# SensorDHT22.net
KiCad netlist of a schematic drawn in EAGLE
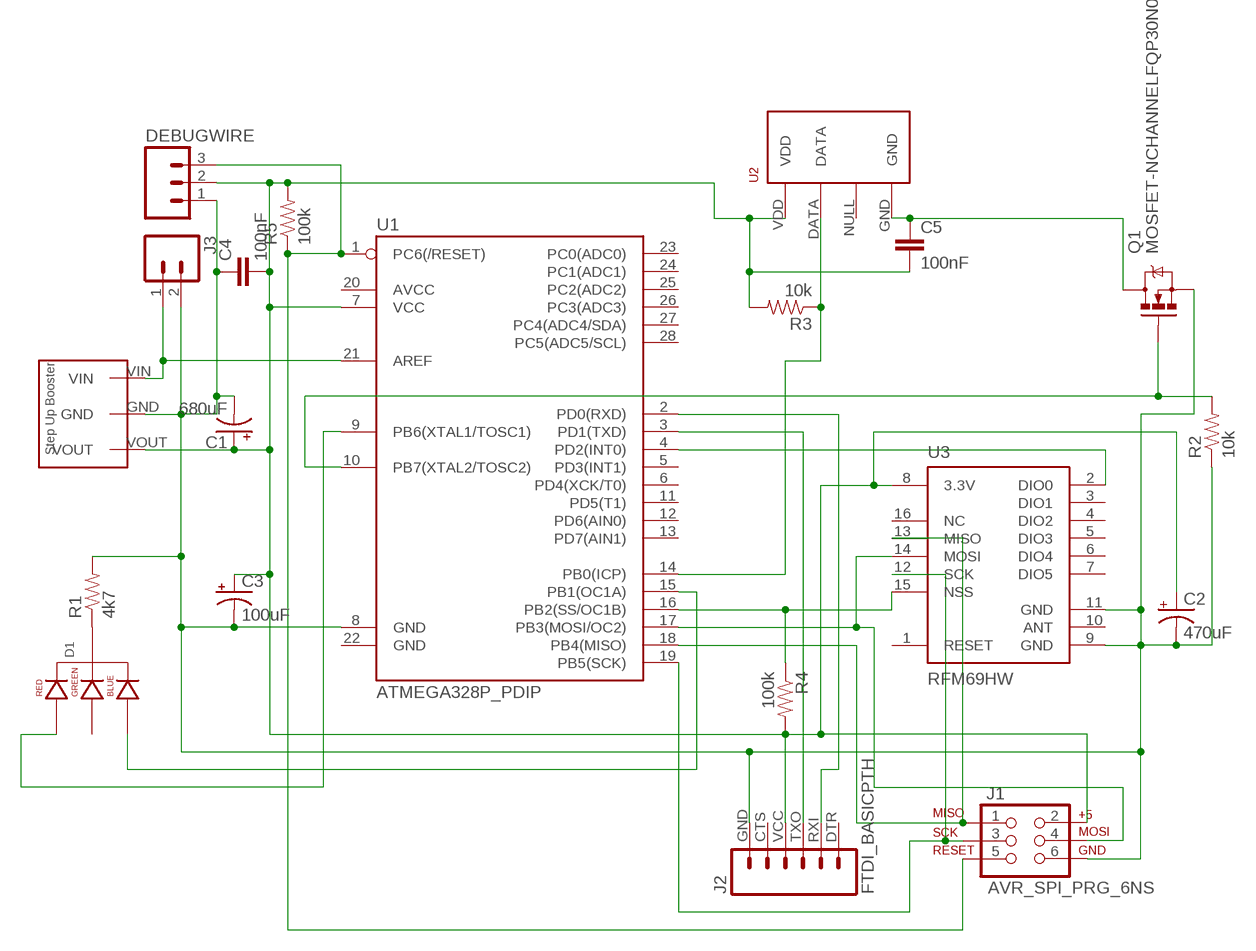
[diagram p0: schematic, sheet 1]

(export (version "E")
  (design (tool "Eeschema 10.0.6"))
  (components
    (comp (ref "C1")
      (value "680uF")
      (footprint "eagle-import:CPOL-RADIAL-100UF-25V")
      (libsource (lib "eagle-import") (part "CAP_POLPTH1"))
    )
    (comp (ref "C2")
      (value "470uF")
      (footprint "eagle-import:CPOL-RADIAL-100UF-25V")
      (libsource (lib "eagle-import") (part "CAP_POLPTH1"))
    )
    (comp (ref "C3")
      (value "100uF")
      (footprint "eagle-import:CPOL-RADIAL-10UF-25V")
      (libsource (lib "eagle-import") (part "CAP_POLPTH2"))
    )
    (comp (ref "C4")
      (value "100nF")
      (footprint "eagle-import:CAP-PTH-SMALL")
      (libsource (lib "eagle-import") (part "CAPPTH"))
    )
    (comp (ref "C5")
      (value "100nF")
      (footprint "eagle-import:CAP-PTH-SMALL")
      (libsource (lib "eagle-import") (part "CAPPTH"))
    )
    (comp (ref "D1")
      (value "LED-RGB-CC-THRUCLEAR")
      (footprint "eagle-import:LED-RGB-THRU")
      (libsource (lib "eagle-import") (part "LED-RGB-CC-THRUCLEAR"))
    )
    (comp (ref "DEBUGWIRE")
      (value "M03PTH")
      (footprint "eagle-import:1X03")
      (libsource (lib "eagle-import") (part "M03PTH"))
    )
    (comp (ref "J1")
      (value "AVR_SPI_PRG_6NS")
      (footprint "eagle-import:2X3-NS")
      (libsource (lib "eagle-import") (part "AVR_SPI_PRG_6NS"))
    )
    (comp (ref "J2")
      (value "FTDI_BASICPTH")
      (footprint "eagle-import:FTDI_BASIC")
      (libsource (lib "eagle-import") (part "FTDI_BASICPTH"))
    )
    (comp (ref "J3")
      (value "M02POLAR")
      (footprint "eagle-import:MOLEX-1X2")
      (libsource (lib "eagle-import") (part "M02POLAR"))
    )
    (comp (ref "Q1")
      (value "MOSFET-NCHANNELFQP30N06L")
      (footprint "eagle-import:TO220V")
      (libsource (lib "eagle-import") (part "MOSFET-NCHANNELFQP30N06L"))
    )
    (comp (ref "R1")
      (value "4k7")
      (footprint "eagle-import:AXIAL-0.4")
      (libsource (lib "eagle-import") (part "RESISTORPTH-1/4W"))
    )
    (comp (ref "R2")
      (value "10k")
      (footprint "eagle-import:AXIAL-0.3")
      (libsource (lib "eagle-import") (part "10KOHM-1/4W-1%(PTH)HORIZ"))
    )
    (comp (ref "R3")
      (value "10k")
      (footprint "eagle-import:AXIAL-0.3")
      (libsource (lib "eagle-import") (part "10KOHM-1/4W-1%(PTH)HORIZ"))
    )
    (comp (ref "R4")
      (value "100k")
      (footprint "eagle-import:AXIAL-0.4")
      (libsource (lib "eagle-import") (part "RESISTORPTH-1/4W"))
    )
    (comp (ref "R5")
      (value "100k")
      (footprint "eagle-import:AXIAL-0.3")
      (libsource (lib "eagle-import") (part "100KOHM-1/4W-5%(PTH)"))
    )
    (comp (ref "STEPUP")
      (value "POLOLU-2563")
      (footprint "eagle-import:POLOLU-2563")
      (libsource (lib "eagle-import") (part "POLOLU-2563"))
    )
    (comp (ref "U1")
      (value "ATMEGA328P_PDIP")
      (footprint "eagle-import:DIL28-3")
      (libsource (lib "eagle-import") (part "ATMEGA328P_PDIP"))
    )
    (comp (ref "U2")
      (value "RHT03_DHT-22_AM2302")
      (footprint "eagle-import:RHT03_DHT-22")
      (libsource (lib "eagle-import") (part "RHT03_DHT-22_AM2302"))
    )
    (comp (ref "U3")
      (value "RFM69HW")
      (footprint "eagle-import:RFM69W-XXXS2")
      (libsource (lib "eagle-import") (part "RFM69HW"))
    )
  )
  (nets
    (net (code "1") (name "Net-(C1-+)") (class "Default")
      (node (ref "C1") (pin "1") (pinfunction "+_1") (pintype "passive"))
      (node (ref "C2") (pin "1") (pinfunction "+_1") (pintype "passive"))
      (node (ref "C3") (pin "1") (pinfunction "+_1") (pintype "passive"))
      (node (ref "C4") (pin "2") (pinfunction "2_2") (pintype "passive"))
      (node (ref "C5") (pin "2") (pinfunction "2_2") (pintype "passive"))
      (node (ref "DEBUGWIRE") (pin "2") (pinfunction "2_2") (pintype "passive"))
      (node (ref "J1") (pin "2") (pinfunction "2_2") (pintype "passive"))
      (node (ref "J2") (pin "VCC") (pinfunction "4_VCC") (pintype "passive"))
      (node (ref "R3") (pin "P$2") (pinfunction "2_P$2") (pintype "passive"))
      (node (ref "R4") (pin "P$2") (pinfunction "2_P$2") (pintype "passive"))
      (node (ref "R5") (pin "P$2") (pinfunction "2_P$2") (pintype "passive"))
      (node (ref "STEPUP") (pin "VOUT") (pinfunction "VOUT_VOUT") (pintype "output"))
      (node (ref "U1") (pin "7") (pinfunction "VCC_7") (pintype "bidirectional"))
      (node (ref "U2") (pin "VDD") (pinfunction "VDD_VDD") (pintype "power_in"))
      (node (ref "U3") (pin "8") (pinfunction "3.3V_8") (pintype "power_in"))
    )
    (net (code "2") (name "Net-(C1--)") (class "Default")
      (node (ref "C1") (pin "2") (pinfunction "-_2") (pintype "passive"))
      (node (ref "C2") (pin "2") (pinfunction "-_2") (pintype "passive"))
      (node (ref "C3") (pin "2") (pinfunction "-_2") (pintype "passive"))
      (node (ref "C4") (pin "1") (pinfunction "1_1") (pintype "passive"))
      (node (ref "DEBUGWIRE") (pin "1") (pinfunction "1_1") (pintype "passive"))
      (node (ref "J1") (pin "6") (pinfunction "6_6") (pintype "passive"))
      (node (ref "J2") (pin "GND") (pinfunction "6_GND") (pintype "passive"))
      (node (ref "J3") (pin "2") (pinfunction "2_2") (pintype "passive"))
      (node (ref "Q1") (pin "3") (pinfunction "S_3") (pintype "passive"))
      (node (ref "R1") (pin "P$2") (pinfunction "2_P$2") (pintype "passive"))
      (node (ref "R2") (pin "P$1") (pinfunction "1_P$1") (pintype "passive"))
      (node (ref "STEPUP") (pin "GND") (pinfunction "GND_GND") (pintype "power_in"))
      (node (ref "U1") (pin "8") (pinfunction "GND_8") (pintype "bidirectional"))
      (node (ref "U3") (pin "11") (pinfunction "GND_11") (pintype "power_in"))
      (node (ref "U3") (pin "9") (pinfunction "GND_9") (pintype "power_in"))
    )
    (net (code "3") (name "Net-(D1-BLUE_CATHODE)") (class "Default")
      (node (ref "D1") (pin "4") (pinfunction "BLUE_CATHODE_4") (pintype "bidirectional"))
      (node (ref "U1") (pin "15") (pinfunction "PB1(OC1A)_15") (pintype "bidirectional"))
    )
    (net (code "4") (name "Net-(D1-CATHODE)") (class "Default")
      (node (ref "D1") (pin "2") (pinfunction "CATHODE_2") (pintype "bidirectional"))
      (node (ref "R1") (pin "P$1") (pinfunction "1_P$1") (pintype "passive"))
    )
    (net (code "5") (name "Net-(D1-RED_CATHODE)") (class "Default")
      (node (ref "D1") (pin "1") (pinfunction "RED_CATHODE_1") (pintype "bidirectional"))
      (node (ref "U1") (pin "9") (pinfunction "PB6(XTAL1/TOSC1)_9") (pintype "bidirectional"))
    )
    (net (code "6") (name "Net-(J2-2)") (class "Default")
      (node (ref "J2") (pin "RXI") (pinfunction "2_RXI") (pintype "passive"))
      (node (ref "U1") (pin "2") (pinfunction "PD0(RXD)_2") (pintype "bidirectional"))
    )
    (net (code "7") (name "Net-(J2-3)") (class "Default")
      (node (ref "J2") (pin "TXO") (pinfunction "3_TXO") (pintype "passive"))
      (node (ref "U1") (pin "3") (pinfunction "PD1(TXD)_3") (pintype "bidirectional"))
    )
    (net (code "8") (name "Net-(Q1-D)") (class "Default")
      (node (ref "C5") (pin "1") (pinfunction "1_1") (pintype "passive"))
      (node (ref "Q1") (pin "2") (pinfunction "D_2") (pintype "passive"))
      (node (ref "U2") (pin "GND") (pinfunction "GND_GND") (pintype "power_in"))
    )
    (net (code "9") (name "Net-(Q1-G)") (class "Default")
      (node (ref "Q1") (pin "1") (pinfunction "G_1") (pintype "passive"))
      (node (ref "R2") (pin "P$2") (pinfunction "2_P$2") (pintype "passive"))
      (node (ref "U1") (pin "10") (pinfunction "PB7(XTAL2/TOSC2)_10") (pintype "bidirectional"))
    )
    (net (code "10") (name "Net-(R3-1)") (class "Default")
      (node (ref "R3") (pin "P$1") (pinfunction "1_P$1") (pintype "passive"))
      (node (ref "U1") (pin "14") (pinfunction "PB0(ICP)_14") (pintype "bidirectional"))
      (node (ref "U2") (pin "DATA") (pinfunction "DATA_DATA") (pintype "bidirectional"))
    )
    (net (code "11") (name "Net-(R4-1)") (class "Default")
      (node (ref "R4") (pin "P$1") (pinfunction "1_P$1") (pintype "passive"))
      (node (ref "U1") (pin "16") (pinfunction "PB2(SS/OC1B)_16") (pintype "bidirectional"))
      (node (ref "U3") (pin "15") (pinfunction "NSS_15") (pintype "input"))
    )
    (net (code "12") (name "Net-(R5-1)") (class "Default")
      (node (ref "DEBUGWIRE") (pin "3") (pinfunction "3_3") (pintype "passive"))
      (node (ref "J1") (pin "5") (pinfunction "5_5") (pintype "passive"))
      (node (ref "R5") (pin "P$1") (pinfunction "1_P$1") (pintype "passive"))
      (node (ref "U1") (pin "1") (pinfunction "PC6(/RESET)_1") (pintype "bidirectional"))
    )
    (net (code "13") (name "Net-(U1-AREF)") (class "Default")
      (node (ref "J3") (pin "1") (pinfunction "1_1") (pintype "passive"))
      (node (ref "STEPUP") (pin "VIN") (pinfunction "VIN_VIN") (pintype "input"))
      (node (ref "U1") (pin "21") (pinfunction "AREF_21") (pintype "bidirectional"))
    )
    (net (code "14") (name "Net-(U1-PB3(MOSI{slash}OC2))") (class "Default")
      (node (ref "J1") (pin "4") (pinfunction "4_4") (pintype "passive"))
      (node (ref "U1") (pin "17") (pinfunction "PB3(MOSI/OC2)_17") (pintype "bidirectional"))
      (node (ref "U3") (pin "14") (pinfunction "MOSI_14") (pintype "input"))
    )
    (net (code "15") (name "Net-(U1-PB4(MISO))") (class "Default")
      (node (ref "J1") (pin "1") (pinfunction "1_1") (pintype "passive"))
      (node (ref "U1") (pin "18") (pinfunction "PB4(MISO)_18") (pintype "bidirectional"))
      (node (ref "U3") (pin "13") (pinfunction "MISO_13") (pintype "bidirectional"))
    )
    (net (code "16") (name "Net-(U1-PB5(SCK))") (class "Default")
      (node (ref "J1") (pin "3") (pinfunction "3_3") (pintype "passive"))
      (node (ref "U1") (pin "19") (pinfunction "PB5(SCK)_19") (pintype "bidirectional"))
      (node (ref "U3") (pin "12") (pinfunction "SCK_12") (pintype "input"))
    )
    (net (code "17") (name "Net-(U1-PD2(INT0))") (class "Default")
      (node (ref "U1") (pin "4") (pinfunction "PD2(INT0)_4") (pintype "bidirectional"))
      (node (ref "U3") (pin "2") (pinfunction "DIO0_2") (pintype "bidirectional"))
    )
    (net (code "18") (name "unconnected-(D1-GREEN_CATHODE-Pad3)") (class "Default")
      (node (ref "D1") (pin "3") (pinfunction "GREEN_CATHODE_3") (pintype "bidirectional"))
    )
    (net (code "19") (name "unconnected-(J2-1-PadDTR)") (class "Default")
      (node (ref "J2") (pin "DTR") (pinfunction "1_DTR") (pintype "passive"))
    )
    (net (code "20") (name "unconnected-(J2-5-PadCTS)") (class "Default")
      (node (ref "J2") (pin "CTS") (pinfunction "5_CTS") (pintype "passive"))
    )
    (net (code "21") (name "unconnected-(U1-AVCC-Pad20)") (class "Default")
      (node (ref "U1") (pin "20") (pinfunction "AVCC_20") (pintype "bidirectional"))
    )
    (net (code "22") (name "unconnected-(U1-GND-Pad22)") (class "Default")
      (node (ref "U1") (pin "22") (pinfunction "GND_22") (pintype "bidirectional"))
    )
    (net (code "23") (name "unconnected-(U1-PC0(ADC0)-Pad23)") (class "Default")
      (node (ref "U1") (pin "23") (pinfunction "PC0(ADC0)_23") (pintype "bidirectional"))
    )
    (net (code "24") (name "unconnected-(U1-PC1(ADC1)-Pad24)") (class "Default")
      (node (ref "U1") (pin "24") (pinfunction "PC1(ADC1)_24") (pintype "bidirectional"))
    )
    (net (code "25") (name "unconnected-(U1-PC2(ADC2)-Pad25)") (class "Default")
      (node (ref "U1") (pin "25") (pinfunction "PC2(ADC2)_25") (pintype "bidirectional"))
    )
    (net (code "26") (name "unconnected-(U1-PC3(ADC3)-Pad26)") (class "Default")
      (node (ref "U1") (pin "26") (pinfunction "PC3(ADC3)_26") (pintype "bidirectional"))
    )
    (net (code "27") (name "unconnected-(U1-PC4(ADC4{slash}SDA)-Pad27)") (class "Default")
      (node (ref "U1") (pin "27") (pinfunction "PC4(ADC4/SDA)_27") (pintype "bidirectional"))
    )
    (net (code "28") (name "unconnected-(U1-PC5(ADC5{slash}SCL)-Pad28)") (class "Default")
      (node (ref "U1") (pin "28") (pinfunction "PC5(ADC5/SCL)_28") (pintype "bidirectional"))
    )
    (net (code "29") (name "unconnected-(U1-PD3(INT1)-Pad5)") (class "Default")
      (node (ref "U1") (pin "5") (pinfunction "PD3(INT1)_5") (pintype "bidirectional"))
    )
    (net (code "30") (name "unconnected-(U1-PD4(XCK{slash}T0)-Pad6)") (class "Default")
      (node (ref "U1") (pin "6") (pinfunction "PD4(XCK/T0)_6") (pintype "bidirectional"))
    )
    (net (code "31") (name "unconnected-(U1-PD5(T1)-Pad11)") (class "Default")
      (node (ref "U1") (pin "11") (pinfunction "PD5(T1)_11") (pintype "bidirectional"))
    )
    (net (code "32") (name "unconnected-(U1-PD6(AIN0)-Pad12)") (class "Default")
      (node (ref "U1") (pin "12") (pinfunction "PD6(AIN0)_12") (pintype "bidirectional"))
    )
    (net (code "33") (name "unconnected-(U1-PD7(AIN1)-Pad13)") (class "Default")
      (node (ref "U1") (pin "13") (pinfunction "PD7(AIN1)_13") (pintype "bidirectional"))
    )
    (net (code "34") (name "unconnected-(U2-PadNULL)") (class "Default")
      (node (ref "U2") (pin "NULL") (pinfunction "NULL_NULL") (pintype "no_connect"))
    )
    (net (code "35") (name "unconnected-(U3-ANT-Pad10)") (class "Default")
      (node (ref "U3") (pin "10") (pinfunction "ANT_10") (pintype "passive"))
    )
    (net (code "36") (name "unconnected-(U3-DIO1-Pad3)") (class "Default")
      (node (ref "U3") (pin "3") (pinfunction "DIO1_3") (pintype "bidirectional"))
    )
    (net (code "37") (name "unconnected-(U3-DIO2-Pad4)") (class "Default")
      (node (ref "U3") (pin "4") (pinfunction "DIO2_4") (pintype "bidirectional"))
    )
    (net (code "38") (name "unconnected-(U3-DIO3-Pad5)") (class "Default")
      (node (ref "U3") (pin "5") (pinfunction "DIO3_5") (pintype "bidirectional"))
    )
    (net (code "39") (name "unconnected-(U3-DIO4-Pad6)") (class "Default")
      (node (ref "U3") (pin "6") (pinfunction "DIO4_6") (pintype "bidirectional"))
    )
    (net (code "40") (name "unconnected-(U3-DIO5-Pad7)") (class "Default")
      (node (ref "U3") (pin "7") (pinfunction "DIO5_7") (pintype "bidirectional"))
    )
    (net (code "41") (name "unconnected-(U3-NC-Pad16)") (class "Default")
      (node (ref "U3") (pin "16") (pinfunction "NC_16") (pintype "bidirectional"))
    )
    (net (code "42") (name "unconnected-(U3-RESET-Pad1)") (class "Default")
      (node (ref "U3") (pin "1") (pinfunction "RESET_1") (pintype "input"))
    )
  )
)
